# main.net
KiCad netlist of a schematic drawn in EAGLE
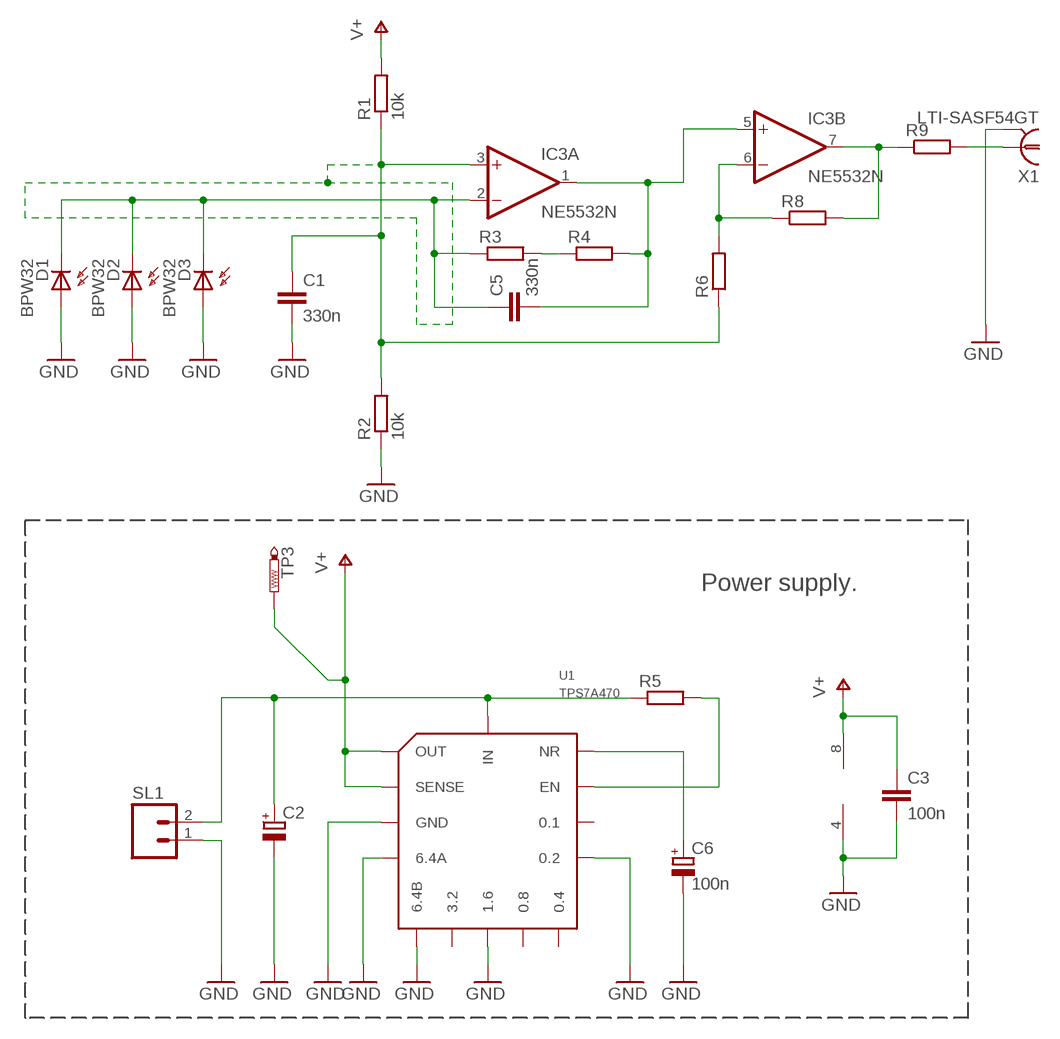
[diagram p0: schematic, sheet 1]

(export (version "E")
  (design (tool "Eeschema 10.0.6"))
  (components
    (comp (ref "C1")
      (value "330n")
      (footprint "eagle-import:C0805")
      (libsource (lib "eagle-import") (part "C-EUC0805"))
    )
    (comp (ref "C2")
      (value "CPOL-EUT/3528-12R")
      (footprint "eagle-import:T_3528-12R")
      (libsource (lib "eagle-import") (part "CPOL-EUT/3528-12R"))
    )
    (comp (ref "C3")
      (value "100n")
      (footprint "eagle-import:C0805")
      (libsource (lib "eagle-import") (part "C-EUC0805"))
    )
    (comp (ref "C5")
      (value "330n")
      (footprint "eagle-import:C1206")
      (libsource (lib "eagle-import") (part "resistor_C-EUC1206"))
    )
    (comp (ref "C6")
      (value "100n")
      (footprint "eagle-import:A_3216-18W")
      (libsource (lib "eagle-import") (part "CPOL-EUA/3216-18W"))
    )
    (comp (ref "D1")
      (value "BPW32")
      (footprint "eagle-import:BPW32")
      (libsource (lib "eagle-import") (part "BPW32"))
    )
    (comp (ref "D2")
      (value "BPW32")
      (footprint "eagle-import:BPW32")
      (libsource (lib "eagle-import") (part "BPW32"))
    )
    (comp (ref "D3")
      (value "BPW32")
      (footprint "eagle-import:BPW32")
      (libsource (lib "eagle-import") (part "BPW32"))
    )
    (comp (ref "IC3")
      (value "NE5532N")
      (footprint "eagle-import:DIL08")
      (libsource (lib "eagle-import") (part "NE5532N"))
    )
    (comp (ref "R1")
      (value "10k")
      (footprint "eagle-import:R0805")
      (libsource (lib "eagle-import") (part "R-EU_R0805"))
    )
    (comp (ref "R2")
      (value "10k")
      (footprint "eagle-import:R0805")
      (libsource (lib "eagle-import") (part "R-EU_R0805"))
    )
    (comp (ref "R3")
      (value "R-EU_MELF0204W")
      (footprint "eagle-import:MINI_MELF-0204W")
      (libsource (lib "eagle-import") (part "resistor_R-EU_MELF0204W"))
    )
    (comp (ref "R4")
      (value "R-EU_MELF0204W")
      (footprint "eagle-import:MINI_MELF-0204W")
      (libsource (lib "eagle-import") (part "resistor_R-EU_MELF0204W"))
    )
    (comp (ref "R5")
      (value "R-EU_M1206")
      (footprint "eagle-import:M1206")
      (libsource (lib "eagle-import") (part "resistor_R-EU_M1206"))
    )
    (comp (ref "R6")
      (value "R-EU_R0805")
      (footprint "eagle-import:R0805")
      (libsource (lib "eagle-import") (part "resistor_R-EU_R0805"))
    )
    (comp (ref "R8")
      (value "R-EU_M0805")
      (footprint "eagle-import:M0805")
      (libsource (lib "eagle-import") (part "resistor_R-EU_M0805"))
    )
    (comp (ref "R9")
      (value "R-EU_0204/2V")
      (footprint "eagle-import:0204V")
      (libsource (lib "eagle-import") (part "resistor_R-EU_0204/2V"))
    )
    (comp (ref "SL1")
      (value "M02")
      (footprint "eagle-import:02P")
      (libsource (lib "eagle-import") (part "M02"))
    )
    (comp (ref "TP3")
      (value "PTR1TP12R")
      (footprint "eagle-import:TP12R")
      (libsource (lib "eagle-import") (part "PTR1TP12R"))
    )
    (comp (ref "U1")
      (value "TPS7A470")
      (footprint "eagle-import:S-PVQFN-N20")
      (libsource (lib "eagle-import") (part "TPS7A470"))
    )
    (comp (ref "X1")
      (value "LTI-SASF54GT")
      (footprint "eagle-import:LTI-SASF54GT")
      (libsource (lib "eagle-import") (part "LTI-SASF54GT"))
    )
  )
  (nets
    (net (code "1") (name "GND") (class "Default")
      (node (ref "C1") (pin "2") (pinfunction "2_2") (pintype "passive"))
      (node (ref "C2") (pin "-") (pinfunction "-_-") (pintype "passive"))
      (node (ref "C3") (pin "2") (pinfunction "2_2") (pintype "passive"))
      (node (ref "C6") (pin "-") (pinfunction "-_-") (pintype "passive"))
      (node (ref "D1") (pin "A") (pinfunction "A_A") (pintype "passive"))
      (node (ref "D2") (pin "A") (pinfunction "A_A") (pintype "passive"))
      (node (ref "D3") (pin "A") (pinfunction "A_A") (pintype "passive"))
      (node (ref "IC3") (pin "4") (pinfunction "V-_4") (pintype "power_in"))
      (node (ref "R2") (pin "1") (pinfunction "1_1") (pintype "passive"))
      (node (ref "SL1") (pin "1") (pinfunction "1_1") (pintype "passive"))
      (node (ref "U1") (pin "11") (pinfunction "0.2_11") (pintype "bidirectional"))
      (node (ref "U1") (pin "17") (pinfunction "GND_17") (pintype "bidirectional"))
      (node (ref "U1") (pin "18") (pinfunction "GND_18") (pintype "bidirectional"))
      (node (ref "U1") (pin "19") (pinfunction "GND_19") (pintype "bidirectional"))
      (node (ref "U1") (pin "2") (pinfunction "GND_2") (pintype "bidirectional"))
      (node (ref "U1") (pin "4") (pinfunction "6.4A_4") (pintype "bidirectional"))
      (node (ref "U1") (pin "5") (pinfunction "6.4B_5") (pintype "bidirectional"))
      (node (ref "U1") (pin "7") (pinfunction "GND_7") (pintype "bidirectional"))
      (node (ref "U1") (pin "8") (pinfunction "1.6_8") (pintype "bidirectional"))
      (node (ref "U1") (pin "EXP") (pinfunction "GND_EXP") (pintype "bidirectional"))
      (node (ref "X1") (pin "2") (pinfunction "2_2") (pintype "passive"))
      (node (ref "X1") (pin "3") (pinfunction "2_3") (pintype "passive"))
      (node (ref "X1") (pin "4") (pinfunction "2_4") (pintype "passive"))
      (node (ref "X1") (pin "5") (pinfunction "2_5") (pintype "passive"))
    )
    (net (code "2") (name "Net-(C2-Pad+)") (class "Default")
      (node (ref "C2") (pin "+") (pinfunction "+_+") (pintype "passive"))
      (node (ref "R5") (pin "1") (pinfunction "1_1") (pintype "passive"))
      (node (ref "SL1") (pin "2") (pinfunction "2_2") (pintype "passive"))
      (node (ref "U1") (pin "15") (pinfunction "IN_15") (pintype "bidirectional"))
      (node (ref "U1") (pin "16") (pinfunction "IN_16") (pintype "bidirectional"))
    )
    (net (code "3") (name "Net-(D1-C)") (class "Default")
      (node (ref "C5") (pin "1") (pinfunction "1_1") (pintype "passive"))
      (node (ref "D1") (pin "K") (pinfunction "C_K") (pintype "passive"))
      (node (ref "D2") (pin "K") (pinfunction "C_K") (pintype "passive"))
      (node (ref "D3") (pin "K") (pinfunction "C_K") (pintype "passive"))
      (node (ref "IC3") (pin "2") (pinfunction "-IN_2") (pintype "input"))
      (node (ref "R3") (pin "1") (pinfunction "1_1") (pintype "passive"))
    )
    (net (code "4") (name "Net-(IC3A-+IN)") (class "Default")
      (node (ref "C1") (pin "1") (pinfunction "1_1") (pintype "passive"))
      (node (ref "IC3") (pin "3") (pinfunction "+IN_3") (pintype "input"))
      (node (ref "R1") (pin "1") (pinfunction "1_1") (pintype "passive"))
      (node (ref "R2") (pin "2") (pinfunction "2_2") (pintype "passive"))
      (node (ref "R6") (pin "1") (pinfunction "1_1") (pintype "passive"))
    )
    (net (code "5") (name "Net-(IC3A-OUT)") (class "Default")
      (node (ref "C5") (pin "2") (pinfunction "2_2") (pintype "passive"))
      (node (ref "IC3") (pin "1") (pinfunction "OUT_1") (pintype "output"))
      (node (ref "IC3") (pin "5") (pinfunction "+IN_5") (pintype "input"))
      (node (ref "R4") (pin "2") (pinfunction "2_2") (pintype "passive"))
    )
    (net (code "6") (name "Net-(IC3B--IN)") (class "Default")
      (node (ref "IC3") (pin "6") (pinfunction "-IN_6") (pintype "input"))
      (node (ref "R6") (pin "2") (pinfunction "2_2") (pintype "passive"))
      (node (ref "R8") (pin "1") (pinfunction "1_1") (pintype "passive"))
    )
    (net (code "7") (name "Net-(IC3B-OUT)") (class "Default")
      (node (ref "IC3") (pin "7") (pinfunction "OUT_7") (pintype "output"))
      (node (ref "R8") (pin "2") (pinfunction "2_2") (pintype "passive"))
      (node (ref "R9") (pin "1") (pinfunction "1_1") (pintype "passive"))
    )
    (net (code "8") (name "Net-(R3-Pad2)") (class "Default")
      (node (ref "R3") (pin "2") (pinfunction "2_2") (pintype "passive"))
      (node (ref "R4") (pin "1") (pinfunction "1_1") (pintype "passive"))
    )
    (net (code "9") (name "Net-(R9-Pad2)") (class "Default")
      (node (ref "R9") (pin "2") (pinfunction "2_2") (pintype "passive"))
      (node (ref "X1") (pin "1") (pinfunction "1_1") (pintype "passive"))
    )
    (net (code "10") (name "Net-(U1-EN)") (class "Default")
      (node (ref "R5") (pin "2") (pinfunction "2_2") (pintype "passive"))
      (node (ref "U1") (pin "13") (pinfunction "EN_13") (pintype "bidirectional"))
    )
    (net (code "11") (name "Net-(U1-NR)") (class "Default")
      (node (ref "C6") (pin "+") (pinfunction "+_+") (pintype "passive"))
      (node (ref "U1") (pin "14") (pinfunction "NR_14") (pintype "bidirectional"))
    )
    (net (code "12") (name "V+") (class "Default")
      (node (ref "C3") (pin "1") (pinfunction "1_1") (pintype "passive"))
      (node (ref "IC3") (pin "8") (pinfunction "V+_8") (pintype "power_in"))
      (node (ref "R1") (pin "2") (pinfunction "2_2") (pintype "passive"))
      (node (ref "TP3") (pin "TP") (pinfunction "TP_TP") (pintype "input"))
      (node (ref "U1") (pin "1") (pinfunction "OUT_1") (pintype "bidirectional"))
      (node (ref "U1") (pin "20") (pinfunction "OUT_20") (pintype "bidirectional"))
      (node (ref "U1") (pin "3") (pinfunction "SENSE_3") (pintype "bidirectional"))
    )
    (net (code "13") (name "unconnected-(U1-0.1-Pad12)") (class "Default")
      (node (ref "U1") (pin "12") (pinfunction "0.1_12") (pintype "bidirectional"))
    )
    (net (code "14") (name "unconnected-(U1-0.4-Pad10)") (class "Default")
      (node (ref "U1") (pin "10") (pinfunction "0.4_10") (pintype "bidirectional"))
    )
    (net (code "15") (name "unconnected-(U1-0.8-Pad9)") (class "Default")
      (node (ref "U1") (pin "9") (pinfunction "0.8_9") (pintype "bidirectional"))
    )
    (net (code "16") (name "unconnected-(U1-3.2-Pad6)") (class "Default")
      (node (ref "U1") (pin "6") (pinfunction "3.2_6") (pintype "bidirectional"))
    )
  )
)
